# R601E.net
KiCad netlist of a schematic drawn in EAGLE
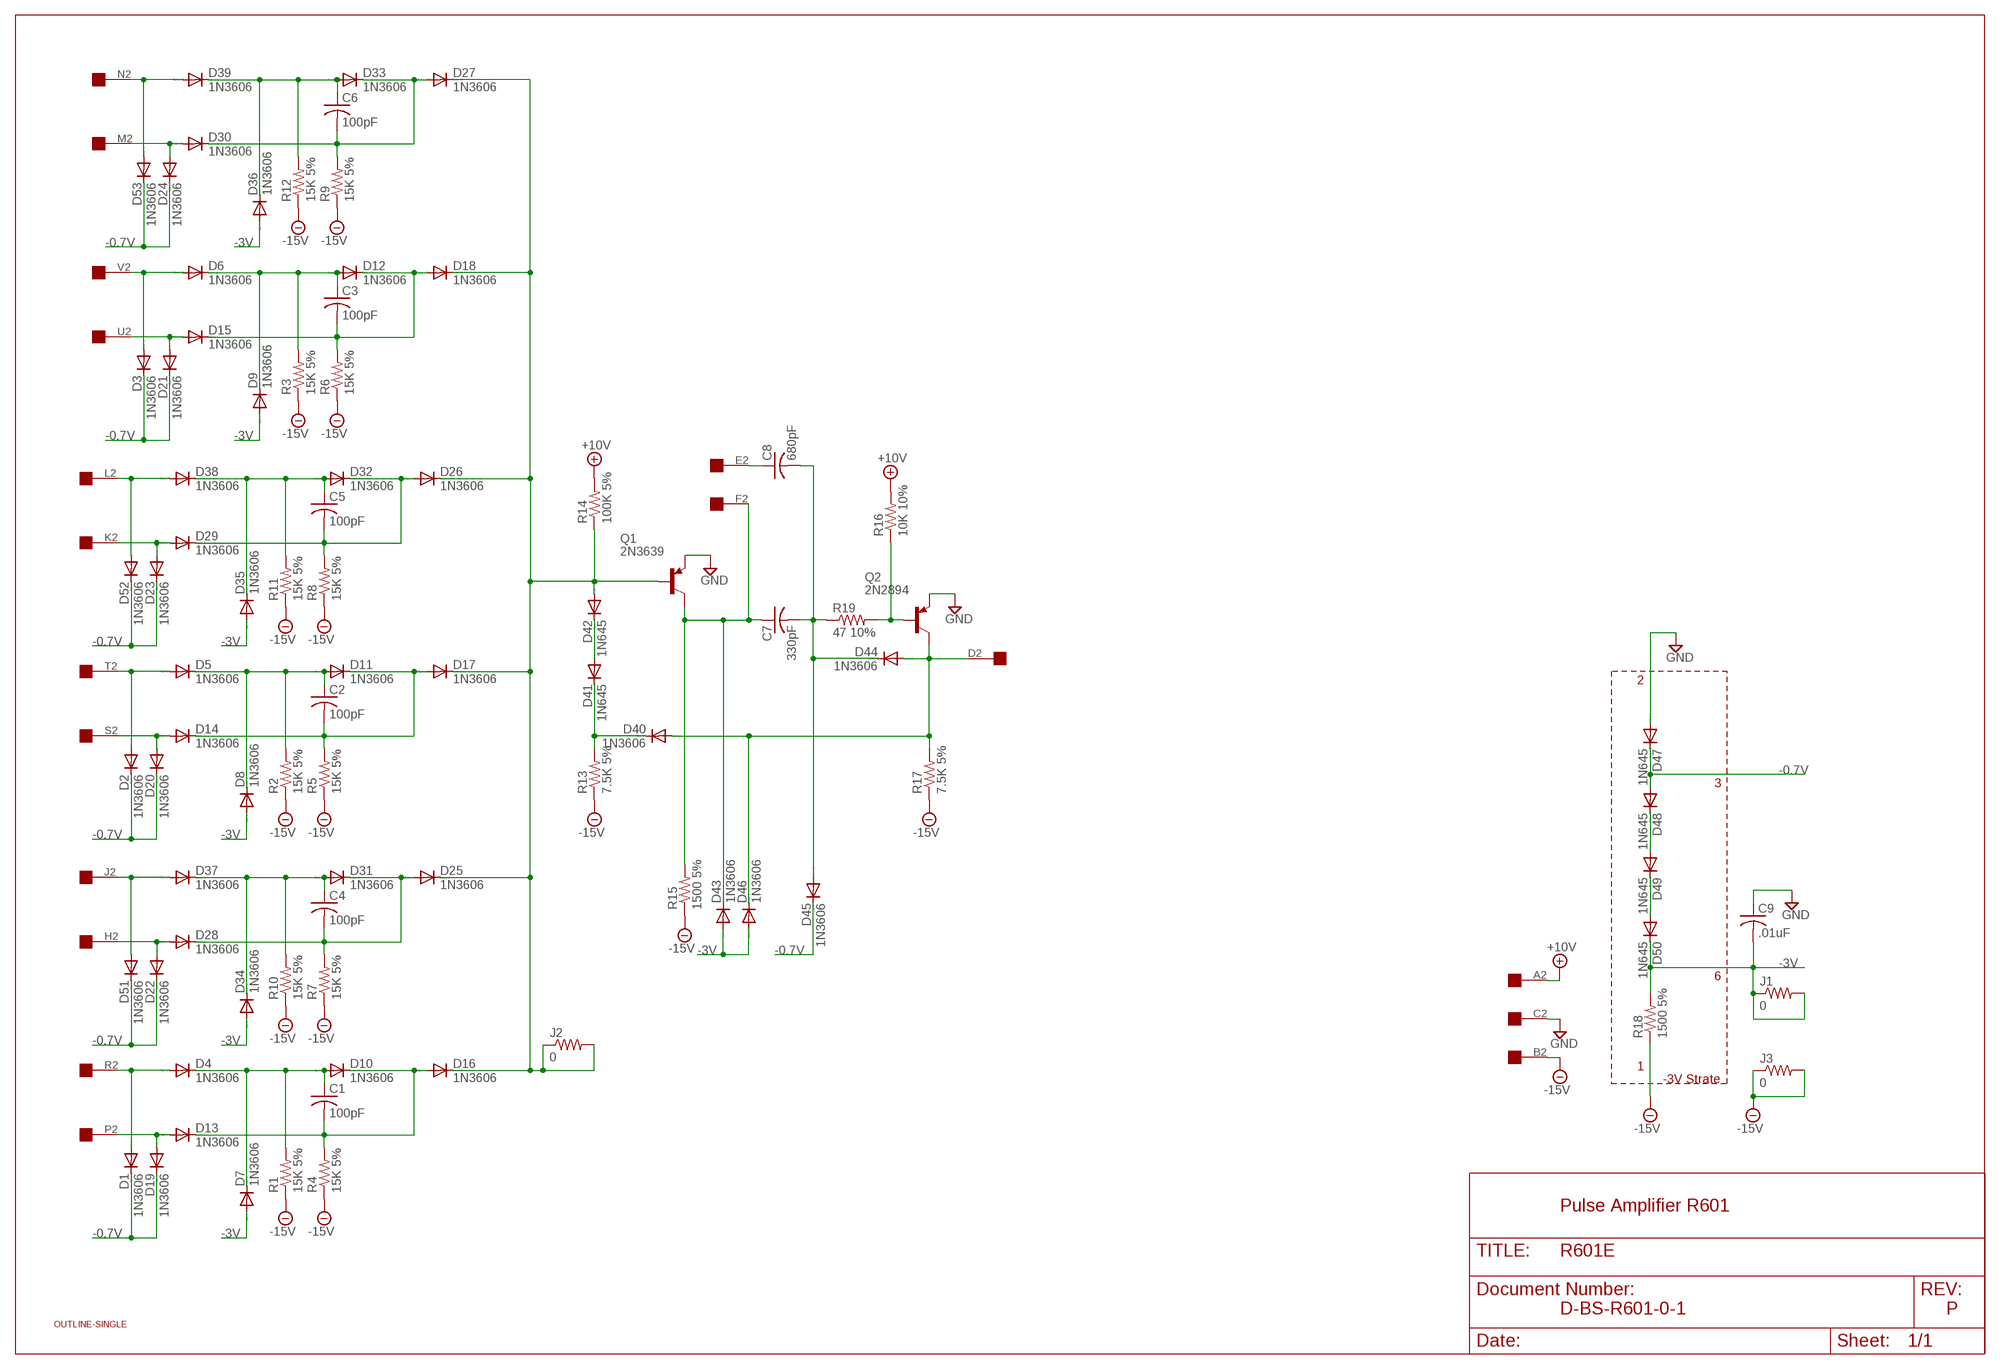
[diagram p0: schematic, sheet 1]

(export (version "E")
  (design (tool "Eeschema 10.0.6"))
  (components
    (comp (ref "C1")
      (value "100pF")
      (footprint "eagle-import:C063-025X075")
      (libsource (lib "eagle-import") (part "C-US"))
    )
    (comp (ref "C2")
      (value "100pF")
      (footprint "eagle-import:C063-025X075")
      (libsource (lib "eagle-import") (part "C-US"))
    )
    (comp (ref "C3")
      (value "100pF")
      (footprint "eagle-import:C063-025X075")
      (libsource (lib "eagle-import") (part "C-US"))
    )
    (comp (ref "C4")
      (value "100pF")
      (footprint "eagle-import:C063-025X075")
      (libsource (lib "eagle-import") (part "C-US"))
    )
    (comp (ref "C5")
      (value "100pF")
      (footprint "eagle-import:C063-025X075")
      (libsource (lib "eagle-import") (part "C-US"))
    )
    (comp (ref "C6")
      (value "100pF")
      (footprint "eagle-import:C063-025X075")
      (libsource (lib "eagle-import") (part "C-US"))
    )
    (comp (ref "C7")
      (value "330pF")
      (footprint "eagle-import:C063-025X075")
      (libsource (lib "eagle-import") (part "C-US"))
    )
    (comp (ref "C8")
      (value "680pF")
      (footprint "eagle-import:C063-025X075")
      (libsource (lib "eagle-import") (part "C-US"))
    )
    (comp (ref "C9")
      (value ".01uF")
      (footprint "eagle-import:C063-025X075")
      (libsource (lib "eagle-import") (part "C-US"))
    )
    (comp (ref "D1")
      (value "1N3606")
      (footprint "eagle-import:DO35-10")
      (libsource (lib "eagle-import") (part "1N4148DO35-10"))
    )
    (comp (ref "D2")
      (value "1N3606")
      (footprint "eagle-import:DO35-10")
      (libsource (lib "eagle-import") (part "1N4148DO35-10"))
    )
    (comp (ref "D3")
      (value "1N3606")
      (footprint "eagle-import:DO35-10")
      (libsource (lib "eagle-import") (part "1N4148DO35-10"))
    )
    (comp (ref "D4")
      (value "1N3606")
      (footprint "eagle-import:DO35-10")
      (libsource (lib "eagle-import") (part "1N4148DO35-10"))
    )
    (comp (ref "D5")
      (value "1N3606")
      (footprint "eagle-import:DO35-10")
      (libsource (lib "eagle-import") (part "1N4148DO35-10"))
    )
    (comp (ref "D6")
      (value "1N3606")
      (footprint "eagle-import:DO35-10")
      (libsource (lib "eagle-import") (part "1N4148DO35-10"))
    )
    (comp (ref "D7")
      (value "1N3606")
      (footprint "eagle-import:DO35-10")
      (libsource (lib "eagle-import") (part "1N4148DO35-10"))
    )
    (comp (ref "D8")
      (value "1N3606")
      (footprint "eagle-import:DO35-10")
      (libsource (lib "eagle-import") (part "1N4148DO35-10"))
    )
    (comp (ref "D9")
      (value "1N3606")
      (footprint "eagle-import:DO35-10")
      (libsource (lib "eagle-import") (part "1N4148DO35-10"))
    )
    (comp (ref "D10")
      (value "1N3606")
      (footprint "eagle-import:DO35-10")
      (libsource (lib "eagle-import") (part "1N4148DO35-10"))
    )
    (comp (ref "D11")
      (value "1N3606")
      (footprint "eagle-import:DO35-10")
      (libsource (lib "eagle-import") (part "1N4148DO35-10"))
    )
    (comp (ref "D12")
      (value "1N3606")
      (footprint "eagle-import:DO35-10")
      (libsource (lib "eagle-import") (part "1N4148DO35-10"))
    )
    (comp (ref "D13")
      (value "1N3606")
      (footprint "eagle-import:DO35-10")
      (libsource (lib "eagle-import") (part "1N4148DO35-10"))
    )
    (comp (ref "D14")
      (value "1N3606")
      (footprint "eagle-import:DO35-10")
      (libsource (lib "eagle-import") (part "1N4148DO35-10"))
    )
    (comp (ref "D15")
      (value "1N3606")
      (footprint "eagle-import:DO35-10")
      (libsource (lib "eagle-import") (part "1N4148DO35-10"))
    )
    (comp (ref "D16")
      (value "1N3606")
      (footprint "eagle-import:DO35-10")
      (libsource (lib "eagle-import") (part "1N4148DO35-10"))
    )
    (comp (ref "D17")
      (value "1N3606")
      (footprint "eagle-import:DO35-10")
      (libsource (lib "eagle-import") (part "1N4148DO35-10"))
    )
    (comp (ref "D18")
      (value "1N3606")
      (footprint "eagle-import:DO35-10")
      (libsource (lib "eagle-import") (part "1N4148DO35-10"))
    )
    (comp (ref "D19")
      (value "1N3606")
      (footprint "eagle-import:DO35-10")
      (libsource (lib "eagle-import") (part "1N4148DO35-10"))
    )
    (comp (ref "D20")
      (value "1N3606")
      (footprint "eagle-import:DO35-10")
      (libsource (lib "eagle-import") (part "1N4148DO35-10"))
    )
    (comp (ref "D21")
      (value "1N3606")
      (footprint "eagle-import:DO35-10")
      (libsource (lib "eagle-import") (part "1N4148DO35-10"))
    )
    (comp (ref "D22")
      (value "1N3606")
      (footprint "eagle-import:DO35-10")
      (libsource (lib "eagle-import") (part "1N4148DO35-10"))
    )
    (comp (ref "D23")
      (value "1N3606")
      (footprint "eagle-import:DO35-10")
      (libsource (lib "eagle-import") (part "1N4148DO35-10"))
    )
    (comp (ref "D24")
      (value "1N3606")
      (footprint "eagle-import:DO35-10")
      (libsource (lib "eagle-import") (part "1N4148DO35-10"))
    )
    (comp (ref "D25")
      (value "1N3606")
      (footprint "eagle-import:DO35-10")
      (libsource (lib "eagle-import") (part "1N4148DO35-10"))
    )
    (comp (ref "D26")
      (value "1N3606")
      (footprint "eagle-import:DO35-10")
      (libsource (lib "eagle-import") (part "1N4148DO35-10"))
    )
    (comp (ref "D27")
      (value "1N3606")
      (footprint "eagle-import:DO35-10")
      (libsource (lib "eagle-import") (part "1N4148DO35-10"))
    )
    (comp (ref "D28")
      (value "1N3606")
      (footprint "eagle-import:DO35-10")
      (libsource (lib "eagle-import") (part "1N4148DO35-10"))
    )
    (comp (ref "D29")
      (value "1N3606")
      (footprint "eagle-import:DO35-10")
      (libsource (lib "eagle-import") (part "1N4148DO35-10"))
    )
    (comp (ref "D30")
      (value "1N3606")
      (footprint "eagle-import:DO35-10")
      (libsource (lib "eagle-import") (part "1N4148DO35-10"))
    )
    (comp (ref "D31")
      (value "1N3606")
      (footprint "eagle-import:DO35-10")
      (libsource (lib "eagle-import") (part "1N4148DO35-10"))
    )
    (comp (ref "D32")
      (value "1N3606")
      (footprint "eagle-import:DO35-10")
      (libsource (lib "eagle-import") (part "1N4148DO35-10"))
    )
    (comp (ref "D33")
      (value "1N3606")
      (footprint "eagle-import:DO35-10")
      (libsource (lib "eagle-import") (part "1N4148DO35-10"))
    )
    (comp (ref "D34")
      (value "1N3606")
      (footprint "eagle-import:DO35-10")
      (libsource (lib "eagle-import") (part "1N4148DO35-10"))
    )
    (comp (ref "D35")
      (value "1N3606")
      (footprint "eagle-import:DO35-10")
      (libsource (lib "eagle-import") (part "1N4148DO35-10"))
    )
    (comp (ref "D36")
      (value "1N3606")
      (footprint "eagle-import:DO35-10")
      (libsource (lib "eagle-import") (part "1N4148DO35-10"))
    )
    (comp (ref "D37")
      (value "1N3606")
      (footprint "eagle-import:DO35-10")
      (libsource (lib "eagle-import") (part "1N4148DO35-10"))
    )
    (comp (ref "D38")
      (value "1N3606")
      (footprint "eagle-import:DO35-10")
      (libsource (lib "eagle-import") (part "1N4148DO35-10"))
    )
    (comp (ref "D39")
      (value "1N3606")
      (footprint "eagle-import:DO35-10")
      (libsource (lib "eagle-import") (part "1N4148DO35-10"))
    )
    (comp (ref "D40")
      (value "1N3606")
      (footprint "eagle-import:DO35-10")
      (libsource (lib "eagle-import") (part "1N4148DO35-10"))
    )
    (comp (ref "D41")
      (value "1N645")
      (footprint "eagle-import:DO35-10")
      (libsource (lib "eagle-import") (part "1N4148DO35-10"))
    )
    (comp (ref "D42")
      (value "1N645")
      (footprint "eagle-import:DO35-10")
      (libsource (lib "eagle-import") (part "1N4148DO35-10"))
    )
    (comp (ref "D43")
      (value "1N3606")
      (footprint "eagle-import:DO35-10")
      (libsource (lib "eagle-import") (part "1N4148DO35-10"))
    )
    (comp (ref "D44")
      (value "1N3606")
      (footprint "eagle-import:DO35-10")
      (libsource (lib "eagle-import") (part "1N4148DO35-10"))
    )
    (comp (ref "D45")
      (value "1N3606")
      (footprint "eagle-import:DO35-10")
      (libsource (lib "eagle-import") (part "1N4148DO35-10"))
    )
    (comp (ref "D46")
      (value "1N3606")
      (footprint "eagle-import:DO35-10")
      (libsource (lib "eagle-import") (part "1N4148DO35-10"))
    )
    (comp (ref "D47")
      (value "1N645")
      (footprint "eagle-import:DO35-10")
      (libsource (lib "eagle-import") (part "1N4148DO35-10"))
    )
    (comp (ref "D48")
      (value "1N645")
      (footprint "eagle-import:DO35-10")
      (libsource (lib "eagle-import") (part "1N4148DO35-10"))
    )
    (comp (ref "D49")
      (value "1N645")
      (footprint "eagle-import:DO35-10")
      (libsource (lib "eagle-import") (part "1N4148DO35-10"))
    )
    (comp (ref "D50")
      (value "1N645")
      (footprint "eagle-import:DO35-10")
      (libsource (lib "eagle-import") (part "1N4148DO35-10"))
    )
    (comp (ref "D51")
      (value "1N3606")
      (footprint "eagle-import:DO35-10")
      (libsource (lib "eagle-import") (part "1N4148DO35-10"))
    )
    (comp (ref "D52")
      (value "1N3606")
      (footprint "eagle-import:DO35-10")
      (libsource (lib "eagle-import") (part "1N4148DO35-10"))
    )
    (comp (ref "D53")
      (value "1N3606")
      (footprint "eagle-import:DO35-10")
      (libsource (lib "eagle-import") (part "1N4148DO35-10"))
    )
    (comp (ref "J1")
      (value "0")
      (footprint "eagle-import:0207_10")
      (libsource (lib "eagle-import") (part "R-US_0207/10"))
    )
    (comp (ref "J2")
      (value "0")
      (footprint "eagle-import:0207_10")
      (libsource (lib "eagle-import") (part "R-US_0207/10"))
    )
    (comp (ref "J3")
      (value "0")
      (footprint "eagle-import:0207_10")
      (libsource (lib "eagle-import") (part "R-US_0207/10"))
    )
    (comp (ref "Q1")
      (value "2N3639")
      (footprint "eagle-import:TO39")
      (libsource (lib "eagle-import") (part "2N2904"))
    )
    (comp (ref "Q2")
      (value "2N2894")
      (footprint "eagle-import:TO39")
      (libsource (lib "eagle-import") (part "2N2904"))
    )
    (comp (ref "R1")
      (value "15K 5%")
      (footprint "eagle-import:0207_10")
      (libsource (lib "eagle-import") (part "R-US_0207/10"))
    )
    (comp (ref "R2")
      (value "15K 5%")
      (footprint "eagle-import:0207_10")
      (libsource (lib "eagle-import") (part "R-US_0207/10"))
    )
    (comp (ref "R3")
      (value "15K 5%")
      (footprint "eagle-import:0207_10")
      (libsource (lib "eagle-import") (part "R-US_0207/10"))
    )
    (comp (ref "R4")
      (value "15K 5%")
      (footprint "eagle-import:0207_10")
      (libsource (lib "eagle-import") (part "R-US_0207/10"))
    )
    (comp (ref "R5")
      (value "15K 5%")
      (footprint "eagle-import:0207_10")
      (libsource (lib "eagle-import") (part "R-US_0207/10"))
    )
    (comp (ref "R6")
      (value "15K 5%")
      (footprint "eagle-import:0207_10")
      (libsource (lib "eagle-import") (part "R-US_0207/10"))
    )
    (comp (ref "R7")
      (value "15K 5%")
      (footprint "eagle-import:0207_10")
      (libsource (lib "eagle-import") (part "R-US_0207/10"))
    )
    (comp (ref "R8")
      (value "15K 5%")
      (footprint "eagle-import:0207_10")
      (libsource (lib "eagle-import") (part "R-US_0207/10"))
    )
    (comp (ref "R9")
      (value "15K 5%")
      (footprint "eagle-import:0207_10")
      (libsource (lib "eagle-import") (part "R-US_0207/10"))
    )
    (comp (ref "R10")
      (value "15K 5%")
      (footprint "eagle-import:0207_10")
      (libsource (lib "eagle-import") (part "R-US_0207/10"))
    )
    (comp (ref "R11")
      (value "15K 5%")
      (footprint "eagle-import:0207_10")
      (libsource (lib "eagle-import") (part "R-US_0207/10"))
    )
    (comp (ref "R12")
      (value "15K 5%")
      (footprint "eagle-import:0207_10")
      (libsource (lib "eagle-import") (part "R-US_0207/10"))
    )
    (comp (ref "R13")
      (value "7.5K 5%")
      (footprint "eagle-import:0207_10")
      (libsource (lib "eagle-import") (part "R-US_0207/10"))
    )
    (comp (ref "R14")
      (value "100K 5%")
      (footprint "eagle-import:0207_10")
      (libsource (lib "eagle-import") (part "R-US_0207/10"))
    )
    (comp (ref "R15")
      (value "1500 5%")
      (footprint "eagle-import:0207_10")
      (libsource (lib "eagle-import") (part "R-US_0207/10"))
    )
    (comp (ref "R16")
      (value "10K 10%")
      (footprint "eagle-import:0207_10")
      (libsource (lib "eagle-import") (part "R-US_0207/10"))
    )
    (comp (ref "R17")
      (value "7.5K 5%")
      (footprint "eagle-import:0207_10")
      (libsource (lib "eagle-import") (part "R-US_0207/10"))
    )
    (comp (ref "R18")
      (value "1500 5%")
      (footprint "eagle-import:0207_10")
      (libsource (lib "eagle-import") (part "R-US_0207/10"))
    )
    (comp (ref "R19")
      (value "47 10%")
      (footprint "eagle-import:0207_10")
      (libsource (lib "eagle-import") (part "R-US_0207/10"))
    )
    (comp (ref "U$1")
      (value "OUTLINE-SINGLE")
      (footprint "eagle-import:SINGLE")
      (libsource (lib "eagle-import") (part "OUTLINE-SINGLE"))
    )
    (comp (ref "U$2")
      (value "EDGE-1")
      (footprint "eagle-import:EDGE-CON1")
      (libsource (lib "eagle-import") (part "EDGE-1"))
    )
  )
  (nets
    (net (code "1") (name "+10V") (class "Default")
      (node (ref "R14") (pin "2") (pinfunction "2_2") (pintype "passive"))
      (node (ref "R16") (pin "2") (pinfunction "2_2") (pintype "passive"))
      (node (ref "U$2") (pin "A2") (pinfunction "1_A2") (pintype "bidirectional"))
    )
    (net (code "2") (name "-15V") (class "Default")
      (node (ref "J3") (pin "1") (pinfunction "1_1") (pintype "passive"))
      (node (ref "J3") (pin "2") (pinfunction "2_2") (pintype "passive"))
      (node (ref "R1") (pin "1") (pinfunction "1_1") (pintype "passive"))
      (node (ref "R10") (pin "1") (pinfunction "1_1") (pintype "passive"))
      (node (ref "R11") (pin "1") (pinfunction "1_1") (pintype "passive"))
      (node (ref "R12") (pin "1") (pinfunction "1_1") (pintype "passive"))
      (node (ref "R13") (pin "1") (pinfunction "1_1") (pintype "passive"))
      (node (ref "R15") (pin "1") (pinfunction "1_1") (pintype "passive"))
      (node (ref "R17") (pin "1") (pinfunction "1_1") (pintype "passive"))
      (node (ref "R18") (pin "1") (pinfunction "1_1") (pintype "passive"))
      (node (ref "R2") (pin "1") (pinfunction "1_1") (pintype "passive"))
      (node (ref "R3") (pin "1") (pinfunction "1_1") (pintype "passive"))
      (node (ref "R4") (pin "1") (pinfunction "1_1") (pintype "passive"))
      (node (ref "R5") (pin "1") (pinfunction "1_1") (pintype "passive"))
      (node (ref "R6") (pin "1") (pinfunction "1_1") (pintype "passive"))
      (node (ref "R7") (pin "1") (pinfunction "1_1") (pintype "passive"))
      (node (ref "R8") (pin "1") (pinfunction "1_1") (pintype "passive"))
      (node (ref "R9") (pin "1") (pinfunction "1_1") (pintype "passive"))
      (node (ref "U$2") (pin "B2") (pinfunction "1_B2") (pintype "bidirectional"))
    )
    (net (code "3") (name "/-0.7V") (class "Default")
      (node (ref "D1") (pin "C") (pinfunction "C_C") (pintype "passive"))
      (node (ref "D19") (pin "C") (pinfunction "C_C") (pintype "passive"))
      (node (ref "D2") (pin "C") (pinfunction "C_C") (pintype "passive"))
      (node (ref "D20") (pin "C") (pinfunction "C_C") (pintype "passive"))
      (node (ref "D21") (pin "C") (pinfunction "C_C") (pintype "passive"))
      (node (ref "D22") (pin "C") (pinfunction "C_C") (pintype "passive"))
      (node (ref "D23") (pin "C") (pinfunction "C_C") (pintype "passive"))
      (node (ref "D24") (pin "C") (pinfunction "C_C") (pintype "passive"))
      (node (ref "D3") (pin "C") (pinfunction "C_C") (pintype "passive"))
      (node (ref "D45") (pin "C") (pinfunction "C_C") (pintype "passive"))
      (node (ref "D47") (pin "C") (pinfunction "C_C") (pintype "passive"))
      (node (ref "D48") (pin "A") (pinfunction "A_A") (pintype "passive"))
      (node (ref "D51") (pin "C") (pinfunction "C_C") (pintype "passive"))
      (node (ref "D52") (pin "C") (pinfunction "C_C") (pintype "passive"))
      (node (ref "D53") (pin "C") (pinfunction "C_C") (pintype "passive"))
    )
    (net (code "4") (name "/-3V") (class "Default")
      (node (ref "C9") (pin "2") (pinfunction "2_2") (pintype "passive"))
      (node (ref "D34") (pin "A") (pinfunction "A_A") (pintype "passive"))
      (node (ref "D35") (pin "A") (pinfunction "A_A") (pintype "passive"))
      (node (ref "D36") (pin "A") (pinfunction "A_A") (pintype "passive"))
      (node (ref "D43") (pin "A") (pinfunction "A_A") (pintype "passive"))
      (node (ref "D46") (pin "A") (pinfunction "A_A") (pintype "passive"))
      (node (ref "D50") (pin "C") (pinfunction "C_C") (pintype "passive"))
      (node (ref "D7") (pin "A") (pinfunction "A_A") (pintype "passive"))
      (node (ref "D8") (pin "A") (pinfunction "A_A") (pintype "passive"))
      (node (ref "D9") (pin "A") (pinfunction "A_A") (pintype "passive"))
      (node (ref "J1") (pin "1") (pinfunction "1_1") (pintype "passive"))
      (node (ref "J1") (pin "2") (pinfunction "2_2") (pintype "passive"))
      (node (ref "R18") (pin "2") (pinfunction "2_2") (pintype "passive"))
    )
    (net (code "5") (name "GND") (class "Default")
      (node (ref "C9") (pin "1") (pinfunction "1_1") (pintype "passive"))
      (node (ref "D47") (pin "A") (pinfunction "A_A") (pintype "passive"))
      (node (ref "Q1") (pin "1") (pinfunction "E_1") (pintype "passive"))
      (node (ref "Q2") (pin "1") (pinfunction "E_1") (pintype "passive"))
      (node (ref "U$2") (pin "C2") (pinfunction "1_C2") (pintype "bidirectional"))
    )
    (net (code "6") (name "Net-(C1-Pad1)") (class "Default")
      (node (ref "C1") (pin "1") (pinfunction "1_1") (pintype "passive"))
      (node (ref "D10") (pin "A") (pinfunction "A_A") (pintype "passive"))
      (node (ref "D4") (pin "C") (pinfunction "C_C") (pintype "passive"))
      (node (ref "D7") (pin "C") (pinfunction "C_C") (pintype "passive"))
      (node (ref "R1") (pin "2") (pinfunction "2_2") (pintype "passive"))
    )
    (net (code "7") (name "Net-(C1-Pad2)") (class "Default")
      (node (ref "C1") (pin "2") (pinfunction "2_2") (pintype "passive"))
      (node (ref "D10") (pin "C") (pinfunction "C_C") (pintype "passive"))
      (node (ref "D13") (pin "C") (pinfunction "C_C") (pintype "passive"))
      (node (ref "D16") (pin "A") (pinfunction "A_A") (pintype "passive"))
      (node (ref "R4") (pin "2") (pinfunction "2_2") (pintype "passive"))
    )
    (net (code "8") (name "Net-(C2-Pad1)") (class "Default")
      (node (ref "C2") (pin "1") (pinfunction "1_1") (pintype "passive"))
      (node (ref "D11") (pin "A") (pinfunction "A_A") (pintype "passive"))
      (node (ref "D5") (pin "C") (pinfunction "C_C") (pintype "passive"))
      (node (ref "D8") (pin "C") (pinfunction "C_C") (pintype "passive"))
      (node (ref "R2") (pin "2") (pinfunction "2_2") (pintype "passive"))
    )
    (net (code "9") (name "Net-(C2-Pad2)") (class "Default")
      (node (ref "C2") (pin "2") (pinfunction "2_2") (pintype "passive"))
      (node (ref "D11") (pin "C") (pinfunction "C_C") (pintype "passive"))
      (node (ref "D14") (pin "C") (pinfunction "C_C") (pintype "passive"))
      (node (ref "D17") (pin "A") (pinfunction "A_A") (pintype "passive"))
      (node (ref "R5") (pin "2") (pinfunction "2_2") (pintype "passive"))
    )
    (net (code "10") (name "Net-(C3-Pad1)") (class "Default")
      (node (ref "C3") (pin "1") (pinfunction "1_1") (pintype "passive"))
      (node (ref "D12") (pin "A") (pinfunction "A_A") (pintype "passive"))
      (node (ref "D6") (pin "C") (pinfunction "C_C") (pintype "passive"))
      (node (ref "D9") (pin "C") (pinfunction "C_C") (pintype "passive"))
      (node (ref "R3") (pin "2") (pinfunction "2_2") (pintype "passive"))
    )
    (net (code "11") (name "Net-(C3-Pad2)") (class "Default")
      (node (ref "C3") (pin "2") (pinfunction "2_2") (pintype "passive"))
      (node (ref "D12") (pin "C") (pinfunction "C_C") (pintype "passive"))
      (node (ref "D15") (pin "C") (pinfunction "C_C") (pintype "passive"))
      (node (ref "D18") (pin "A") (pinfunction "A_A") (pintype "passive"))
      (node (ref "R6") (pin "2") (pinfunction "2_2") (pintype "passive"))
    )
    (net (code "12") (name "Net-(C4-Pad1)") (class "Default")
      (node (ref "C4") (pin "1") (pinfunction "1_1") (pintype "passive"))
      (node (ref "D31") (pin "A") (pinfunction "A_A") (pintype "passive"))
      (node (ref "D34") (pin "C") (pinfunction "C_C") (pintype "passive"))
      (node (ref "D37") (pin "C") (pinfunction "C_C") (pintype "passive"))
      (node (ref "R10") (pin "2") (pinfunction "2_2") (pintype "passive"))
    )
    (net (code "13") (name "Net-(C4-Pad2)") (class "Default")
      (node (ref "C4") (pin "2") (pinfunction "2_2") (pintype "passive"))
      (node (ref "D25") (pin "A") (pinfunction "A_A") (pintype "passive"))
      (node (ref "D28") (pin "C") (pinfunction "C_C") (pintype "passive"))
      (node (ref "D31") (pin "C") (pinfunction "C_C") (pintype "passive"))
      (node (ref "R7") (pin "2") (pinfunction "2_2") (pintype "passive"))
    )
    (net (code "14") (name "Net-(C5-Pad1)") (class "Default")
      (node (ref "C5") (pin "1") (pinfunction "1_1") (pintype "passive"))
      (node (ref "D32") (pin "A") (pinfunction "A_A") (pintype "passive"))
      (node (ref "D35") (pin "C") (pinfunction "C_C") (pintype "passive"))
      (node (ref "D38") (pin "C") (pinfunction "C_C") (pintype "passive"))
      (node (ref "R11") (pin "2") (pinfunction "2_2") (pintype "passive"))
    )
    (net (code "15") (name "Net-(C5-Pad2)") (class "Default")
      (node (ref "C5") (pin "2") (pinfunction "2_2") (pintype "passive"))
      (node (ref "D26") (pin "A") (pinfunction "A_A") (pintype "passive"))
      (node (ref "D29") (pin "C") (pinfunction "C_C") (pintype "passive"))
      (node (ref "D32") (pin "C") (pinfunction "C_C") (pintype "passive"))
      (node (ref "R8") (pin "2") (pinfunction "2_2") (pintype "passive"))
    )
    (net (code "16") (name "Net-(C6-Pad1)") (class "Default")
      (node (ref "C6") (pin "1") (pinfunction "1_1") (pintype "passive"))
      (node (ref "D33") (pin "A") (pinfunction "A_A") (pintype "passive"))
      (node (ref "D36") (pin "C") (pinfunction "C_C") (pintype "passive"))
      (node (ref "D39") (pin "C") (pinfunction "C_C") (pintype "passive"))
      (node (ref "R12") (pin "2") (pinfunction "2_2") (pintype "passive"))
    )
    (net (code "17") (name "Net-(C6-Pad2)") (class "Default")
      (node (ref "C6") (pin "2") (pinfunction "2_2") (pintype "passive"))
      (node (ref "D27") (pin "A") (pinfunction "A_A") (pintype "passive"))
      (node (ref "D30") (pin "C") (pinfunction "C_C") (pintype "passive"))
      (node (ref "D33") (pin "C") (pinfunction "C_C") (pintype "passive"))
      (node (ref "R9") (pin "2") (pinfunction "2_2") (pintype "passive"))
    )
    (net (code "18") (name "Net-(C7-Pad2)") (class "Default")
      (node (ref "C7") (pin "2") (pinfunction "2_2") (pintype "passive"))
      (node (ref "C8") (pin "2") (pinfunction "2_2") (pintype "passive"))
      (node (ref "D44") (pin "C") (pinfunction "C_C") (pintype "passive"))
      (node (ref "D45") (pin "A") (pinfunction "A_A") (pintype "passive"))
      (node (ref "R19") (pin "1") (pinfunction "1_1") (pintype "passive"))
    )
    (net (code "19") (name "Net-(D40-PadC)") (class "Default")
      (node (ref "D40") (pin "C") (pinfunction "C_C") (pintype "passive"))
      (node (ref "D41") (pin "C") (pinfunction "C_C") (pintype "passive"))
      (node (ref "R13") (pin "2") (pinfunction "2_2") (pintype "passive"))
    )
    (net (code "20") (name "Net-(D41-PadA)") (class "Default")
      (node (ref "D41") (pin "A") (pinfunction "A_A") (pintype "passive"))
      (node (ref "D42") (pin "C") (pinfunction "C_C") (pintype "passive"))
    )
    (net (code "21") (name "Net-(D48-PadC)") (class "Default")
      (node (ref "D48") (pin "C") (pinfunction "C_C") (pintype "passive"))
      (node (ref "D49") (pin "A") (pinfunction "A_A") (pintype "passive"))
    )
    (net (code "22") (name "Net-(D49-PadC)") (class "Default")
      (node (ref "D49") (pin "C") (pinfunction "C_C") (pintype "passive"))
      (node (ref "D50") (pin "A") (pinfunction "A_A") (pintype "passive"))
    )
    (net (code "23") (name "Net-(Q1-B)") (class "Default")
      (node (ref "D16") (pin "C") (pinfunction "C_C") (pintype "passive"))
      (node (ref "D17") (pin "C") (pinfunction "C_C") (pintype "passive"))
      (node (ref "D18") (pin "C") (pinfunction "C_C") (pintype "passive"))
      (node (ref "D25") (pin "C") (pinfunction "C_C") (pintype "passive"))
      (node (ref "D26") (pin "C") (pinfunction "C_C") (pintype "passive"))
      (node (ref "D27") (pin "C") (pinfunction "C_C") (pintype "passive"))
      (node (ref "D42") (pin "A") (pinfunction "A_A") (pintype "passive"))
      (node (ref "J2") (pin "1") (pinfunction "1_1") (pintype "passive"))
      (node (ref "J2") (pin "2") (pinfunction "2_2") (pintype "passive"))
      (node (ref "Q1") (pin "2") (pinfunction "B_2") (pintype "passive"))
      (node (ref "R14") (pin "1") (pinfunction "1_1") (pintype "passive"))
    )
    (net (code "24") (name "Net-(Q1-C)") (class "Default")
      (node (ref "C7") (pin "1") (pinfunction "1_1") (pintype "passive"))
      (node (ref "D43") (pin "C") (pinfunction "C_C") (pintype "passive"))
      (node (ref "Q1") (pin "3") (pinfunction "C_3") (pintype "passive"))
      (node (ref "R15") (pin "2") (pinfunction "2_2") (pintype "passive"))
      (node (ref "U$2") (pin "F2") (pinfunction "1_F2") (pintype "bidirectional"))
    )
    (net (code "25") (name "Net-(Q2-B)") (class "Default")
      (node (ref "Q2") (pin "2") (pinfunction "B_2") (pintype "passive"))
      (node (ref "R16") (pin "1") (pinfunction "1_1") (pintype "passive"))
      (node (ref "R19") (pin "2") (pinfunction "2_2") (pintype "passive"))
    )
    (net (code "26") (name "Net-(Q2-C)") (class "Default")
      (node (ref "D40") (pin "A") (pinfunction "A_A") (pintype "passive"))
      (node (ref "D44") (pin "A") (pinfunction "A_A") (pintype "passive"))
      (node (ref "D46") (pin "C") (pinfunction "C_C") (pintype "passive"))
      (node (ref "Q2") (pin "3") (pinfunction "C_3") (pintype "passive"))
      (node (ref "R17") (pin "2") (pinfunction "2_2") (pintype "passive"))
      (node (ref "U$2") (pin "D2") (pinfunction "1_D2") (pintype "bidirectional"))
    )
    (net (code "27") (name "Net-(U$2E-1)") (class "Default")
      (node (ref "C8") (pin "1") (pinfunction "1_1") (pintype "passive"))
      (node (ref "U$2") (pin "E2") (pinfunction "1_E2") (pintype "bidirectional"))
    )
    (net (code "28") (name "Net-(U$2G-1)") (class "Default")
      (node (ref "D22") (pin "A") (pinfunction "A_A") (pintype "passive"))
      (node (ref "D28") (pin "A") (pinfunction "A_A") (pintype "passive"))
      (node (ref "U$2") (pin "H2") (pinfunction "1_H2") (pintype "bidirectional"))
    )
    (net (code "29") (name "Net-(U$2H-1)") (class "Default")
      (node (ref "D37") (pin "A") (pinfunction "A_A") (pintype "passive"))
      (node (ref "D51") (pin "A") (pinfunction "A_A") (pintype "passive"))
      (node (ref "U$2") (pin "J2") (pinfunction "1_J2") (pintype "bidirectional"))
    )
    (net (code "30") (name "Net-(U$2I-1)") (class "Default")
      (node (ref "D23") (pin "A") (pinfunction "A_A") (pintype "passive"))
      (node (ref "D29") (pin "A") (pinfunction "A_A") (pintype "passive"))
      (node (ref "U$2") (pin "K2") (pinfunction "1_K2") (pintype "bidirectional"))
    )
    (net (code "31") (name "Net-(U$2J-1)") (class "Default")
      (node (ref "D38") (pin "A") (pinfunction "A_A") (pintype "passive"))
      (node (ref "D52") (pin "A") (pinfunction "A_A") (pintype "passive"))
      (node (ref "U$2") (pin "L2") (pinfunction "1_L2") (pintype "bidirectional"))
    )
    (net (code "32") (name "Net-(U$2K-1)") (class "Default")
      (node (ref "D24") (pin "A") (pinfunction "A_A") (pintype "passive"))
      (node (ref "D30") (pin "A") (pinfunction "A_A") (pintype "passive"))
      (node (ref "U$2") (pin "M2") (pinfunction "1_M2") (pintype "bidirectional"))
    )
    (net (code "33") (name "Net-(U$2L-1)") (class "Default")
      (node (ref "D39") (pin "A") (pinfunction "A_A") (pintype "passive"))
      (node (ref "D53") (pin "A") (pinfunction "A_A") (pintype "passive"))
      (node (ref "U$2") (pin "N2") (pinfunction "1_N2") (pintype "bidirectional"))
    )
    (net (code "34") (name "Net-(U$2M-1)") (class "Default")
      (node (ref "D13") (pin "A") (pinfunction "A_A") (pintype "passive"))
      (node (ref "D19") (pin "A") (pinfunction "A_A") (pintype "passive"))
      (node (ref "U$2") (pin "P2") (pinfunction "1_P2") (pintype "bidirectional"))
    )
    (net (code "35") (name "Net-(U$2N-1)") (class "Default")
      (node (ref "D1") (pin "A") (pinfunction "A_A") (pintype "passive"))
      (node (ref "D4") (pin "A") (pinfunction "A_A") (pintype "passive"))
      (node (ref "U$2") (pin "R2") (pinfunction "1_R2") (pintype "bidirectional"))
    )
    (net (code "36") (name "Net-(U$2O-1)") (class "Default")
      (node (ref "D14") (pin "A") (pinfunction "A_A") (pintype "passive"))
      (node (ref "D20") (pin "A") (pinfunction "A_A") (pintype "passive"))
      (node (ref "U$2") (pin "S2") (pinfunction "1_S2") (pintype "bidirectional"))
    )
    (net (code "37") (name "Net-(U$2P-1)") (class "Default")
      (node (ref "D2") (pin "A") (pinfunction "A_A") (pintype "passive"))
      (node (ref "D5") (pin "A") (pinfunction "A_A") (pintype "passive"))
      (node (ref "U$2") (pin "T2") (pinfunction "1_T2") (pintype "bidirectional"))
    )
    (net (code "38") (name "Net-(U$2Q-1)") (class "Default")
      (node (ref "D15") (pin "A") (pinfunction "A_A") (pintype "passive"))
      (node (ref "D21") (pin "A") (pinfunction "A_A") (pintype "passive"))
      (node (ref "U$2") (pin "U2") (pinfunction "1_U2") (pintype "bidirectional"))
    )
    (net (code "39") (name "Net-(U$2R-1)") (class "Default")
      (node (ref "D3") (pin "A") (pinfunction "A_A") (pintype "passive"))
      (node (ref "D6") (pin "A") (pinfunction "A_A") (pintype "passive"))
      (node (ref "U$2") (pin "V2") (pinfunction "1_V2") (pintype "bidirectional"))
    )
  )
)
